# CH2-Input.net
KiCad netlist of a schematic drawn in Altium Designer
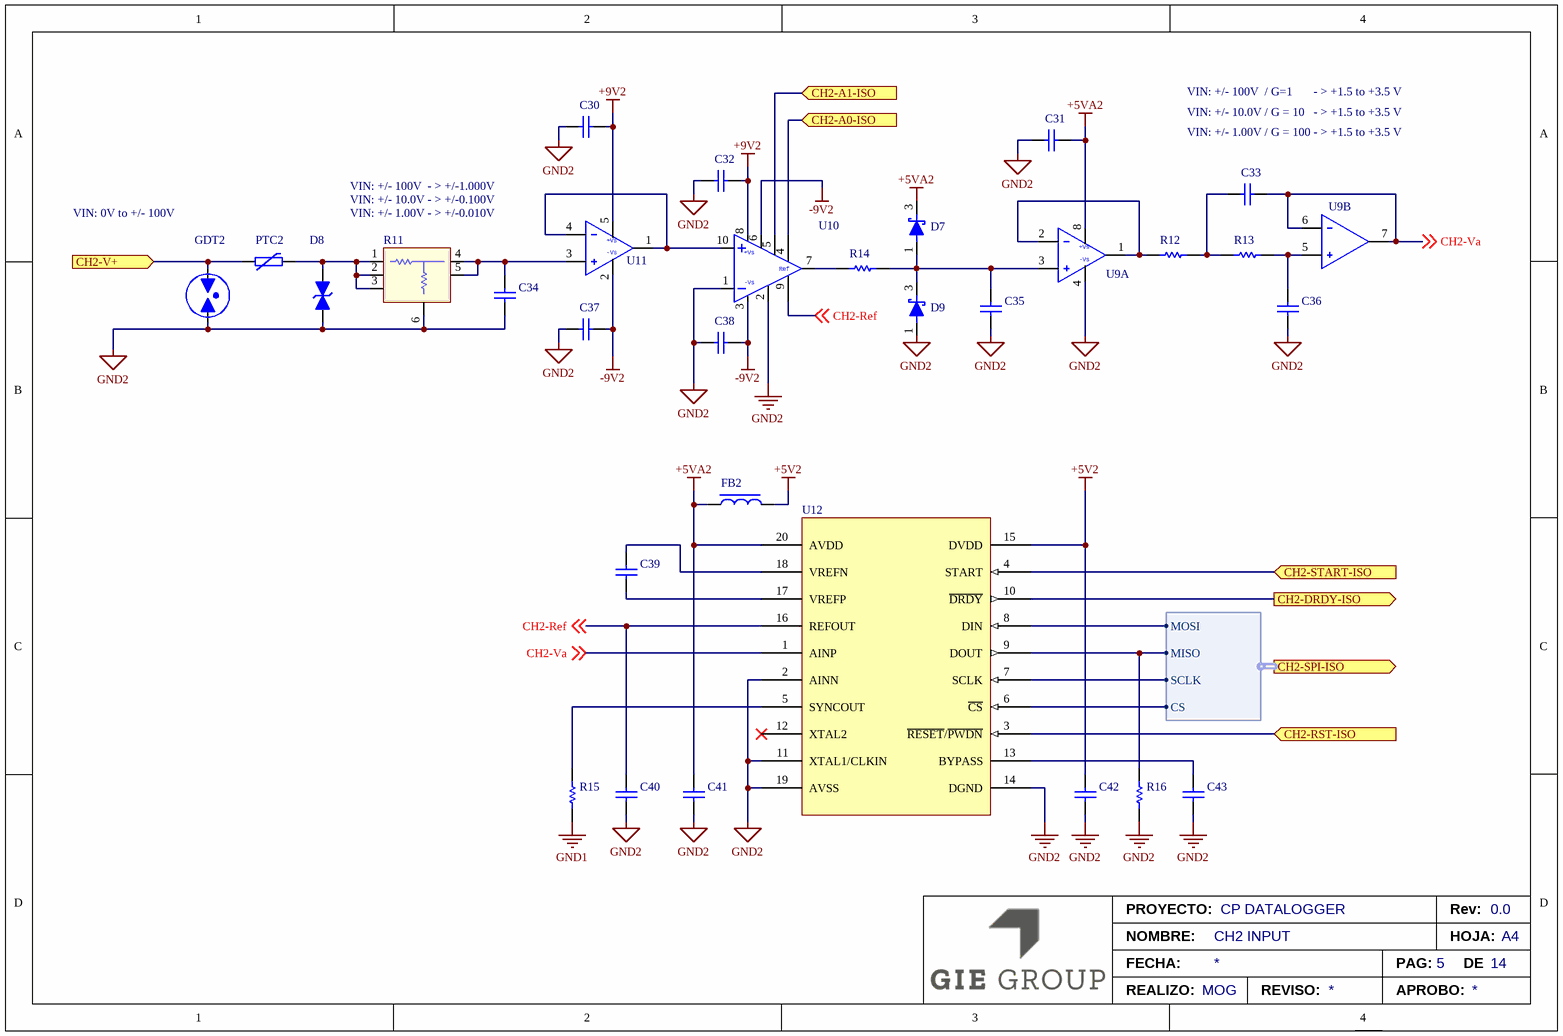
[diagram p0: CH2-Input.SchDoc]

(export (version "E")
  (design (tool "Eeschema 10.0.6"))
  (components
    (comp (ref "C30")
      (value "C0603C104K5RACAUTO")
      (footprint "CAP-0603")
      (description "CAP CER 0.1uF 50V X7R 0603")
      (fields (field (name "MANUFACTURER") "Kemet") (field (name "TOLERANCE") "10%"))
      (libsource (lib "Kemet") (part "C0603C104K5RACAUTO"))
    )
    (comp (ref "C31")
      (value "C0603C104K5RACAUTO")
      (footprint "CAP-0603")
      (description "CAP CER 0.1uF 50V X7R 0603")
      (fields (field (name "MANUFACTURER") "Kemet") (field (name "TOLERANCE") "10%"))
      (libsource (lib "Kemet") (part "C0603C104K5RACAUTO"))
    )
    (comp (ref "C32")
      (value "C0603C104K5RACAUTO")
      (footprint "CAP-0603")
      (description "CAP CER 0.1uF 50V X7R 0603")
      (fields (field (name "MANUFACTURER") "Kemet") (field (name "TOLERANCE") "10%"))
      (libsource (lib "Kemet") (part "C0603C104K5RACAUTO"))
    )
    (comp (ref "C33")
      (value "C0603C162J5GAC7867")
      (footprint "CAP-0603")
      (description "CAP CER 1600´pF 50V C0G 0603")
      (fields (field (name "MANUFACTURER") "Kemet") (field (name "TOLERANCE") "5%"))
      (libsource (lib "Kemet") (part "C0603C162J5GAC7867"))
    )
    (comp (ref "C34")
      (value "C0603C161J1GAC7867")
      (footprint "CAP-0603")
      (description "CAP CER 750´pF 50V C0G 0603")
      (fields (field (name "MANUFACTURER") "Kemet") (field (name "TOLERANCE") "5%"))
      (libsource (lib "Kemet") (part "C0603C751J5GAC7867"))
    )
    (comp (ref "C35")
      (value "C0603C162J5GAC7867")
      (footprint "CAP-0603")
      (description "CAP CER 1600´pF 50V C0G 0603")
      (fields (field (name "MANUFACTURER") "Kemet") (field (name "TOLERANCE") "5%"))
      (libsource (lib "Kemet") (part "C0603C162J5GAC7867"))
    )
    (comp (ref "C36")
      (value "C0603C161J1GAC7867")
      (footprint "CAP-0603")
      (description "CAP CER 160 pF 100V C0G 0603")
      (fields (field (name "MANUFACTURER") "Kemet") (field (name "TOLERANCE") "5%"))
      (libsource (lib "Kemet") (part "C0603C161J1GAC7867"))
    )
    (comp (ref "C37")
      (value "C0603C104K5RACAUTO")
      (footprint "CAP-0603")
      (description "CAP CER 0.1uF 50V X7R 0603")
      (fields (field (name "MANUFACTURER") "Kemet") (field (name "TOLERANCE") "10%"))
      (libsource (lib "Kemet") (part "C0603C104K5RACAUTO"))
    )
    (comp (ref "C38")
      (value "C0603C104K5RACAUTO")
      (footprint "CAP-0603")
      (description "CAP CER 0.1uF 50V X7R 0603")
      (fields (field (name "MANUFACTURER") "Kemet") (field (name "TOLERANCE") "10%"))
      (libsource (lib "Kemet") (part "C0603C104K5RACAUTO"))
    )
    (comp (ref "C39")
      (value "C0603C105M3RAC7867")
      (footprint "CAP-0603")
      (description "CAP CER 1uF 25V X7R 0603")
      (fields (field (name "MANUFACTURER") "Kemet") (field (name "TOLERANCE") "20%"))
      (libsource (lib "Kemet") (part "C0603C105M3RAC7867"))
    )
    (comp (ref "C40")
      (value "C0603C105M3RAC7867")
      (footprint "CAP-0603")
      (description "CAP CER 1uF 25V X7R 0603")
      (fields (field (name "MANUFACTURER") "Kemet") (field (name "TOLERANCE") "20%"))
      (libsource (lib "Kemet") (part "C0603C105M3RAC7867"))
    )
    (comp (ref "C41")
      (value "C0603C105M3RAC7867")
      (footprint "CAP-0603")
      (description "CAP CER 1uF 25V X7R 0603")
      (fields (field (name "MANUFACTURER") "Kemet") (field (name "TOLERANCE") "20%"))
      (libsource (lib "Kemet") (part "C0603C105M3RAC7867"))
    )
    (comp (ref "C42")
      (value "C0603C105M3RAC7867")
      (footprint "CAP-0603")
      (description "CAP CER 1uF 25V X7R 0603")
      (fields (field (name "MANUFACTURER") "Kemet") (field (name "TOLERANCE") "20%"))
      (libsource (lib "Kemet") (part "C0603C105M3RAC7867"))
    )
    (comp (ref "C43")
      (value "C0603C105M3RAC7867")
      (footprint "CAP-0603")
      (description "CAP CER 1uF 25V X7R 0603")
      (fields (field (name "MANUFACTURER") "Kemet") (field (name "TOLERANCE") "20%"))
      (libsource (lib "Kemet") (part "C0603C105M3RAC7867"))
    )
    (comp (ref "D7")
      (value "NSVBAT54WT1G")
      (footprint "SOT-323-3")
      (description "Schottky Diode 30V 200mA SOT323")
      (fields (field (name "MANUFACTURER") "OnSemiconductor"))
      (libsource (lib "OnSemiconductors") (part "NSVBAT54WT1G"))
    )
    (comp (ref "D8")
      (value "~")
      (footprint "SMC - BIIDIR")
      (description "TVS Diode 1.5kW 130V 5% Bi-Directional")
      (fields (field (name "MANUFACTURER") "Littelfuse"))
      (libsource (lib "Littlelfuse") (part "1.5SMC130CA"))
    )
    (comp (ref "D9")
      (value "~")
      (footprint "SOT-323-3")
      (description "Schottky Diode 30V 200mA SOT323")
      (fields (field (name "MANUFACTURER") "OnSemiconductor"))
      (libsource (lib "OnSemiconductors") (part "NSVBAT54WT1G"))
    )
    (comp (ref "FB2")
      (value "Z0603C121GPWZT")
      (footprint "IND-0603")
      (description "Ferrite Bead 120Ohms 900mA 25% DCR=130m")
      (fields (field (name "MANUFACTURER") "Kemet"))
      (libsource (lib "Kemet") (part "Z0603C121GPWZT"))
    )
    (comp (ref "GDT2")
      (value "~")
      (footprint "LITTLELFUSE-CG5XXXLTR")
      (description "Gas Discharge Tube 145V")
      (fields (field (name "MANUFACTURER") "Littelfuse"))
      (libsource (lib "Littlelfuse") (part "CG5145LTR"))
    )
    (comp (ref "PTC2")
      (value "~")
      (footprint "LITTLELFUSE-72R020X")
      (description "PTC Polyfuse Radial 72V 0.2A")
      (fields (field (name "MANUFACTURER") "Littlelfuse"))
      (libsource (lib "Littlelfuse") (part "72R020XPR"))
    )
    (comp (ref "R11")
      (value "~")
      (footprint "CADDOCK - HVD5-B20M-050-05")
      (description "20M ohm 0.05% 5ppm Voltage Divider")
      (fields (field (name "MANUFACTURER") "Caddock"))
      (libsource (lib "Caddock") (part "HVD5-B20M-050-05"))
    )
    (comp (ref "R12")
      (value "RC0603FR-07113KL")
      (footprint "RES-0603")
      (description "RES SMD 113K OHM 1% 1/10W 0603")
      (fields (field (name "TOLERANCE") "1%") (field (name "MANUFACTURER") "Yageo"))
      (libsource (lib "Yageo") (part "RC0603FR-07113KL"))
    )
    (comp (ref "R13")
      (value "RC0603FR-07887KL")
      (footprint "RES-0603")
      (description "RES SMD 887K OHM 1% 1/10W 0603")
      (fields (field (name "TOLERANCE") "1%") (field (name "MANUFACTURER") "Yageo"))
      (libsource (lib "Yageo") (part "RC0603FR-07887KL"))
    )
    (comp (ref "R14")
      (value "RC0603FR-07100KL")
      (footprint "RES-0603")
      (description "RES SMD 100K OHM 1% 1/10W 0603")
      (fields (field (name "TOLERANCE") "1%") (field (name "MANUFACTURER") "Yageo"))
      (libsource (lib "Yageo") (part "RC0603FR-07100KL"))
    )
    (comp (ref "R15")
      (value "RC0603FR-071ML")
      (footprint "RES-0603")
      (description "RES SMD 1M OHM 1% 1/10W 0603")
      (fields (field (name "TOLERANCE") "1%") (field (name "MANUFACTURER") "Yageo"))
      (libsource (lib "Yageo") (part "RC0603FR-071ML"))
    )
    (comp (ref "R16")
      (value "RC0603FR-071ML")
      (footprint "RES-0603")
      (description "RES SMD 1M OHM 1% 1/10W 0603")
      (fields (field (name "TOLERANCE") "1%") (field (name "MANUFACTURER") "Yageo"))
      (libsource (lib "Yageo") (part "RC0603FR-071ML"))
    )
    (comp (ref "U9")
      (value "~")
      (footprint "MSOP8")
      (description "Dual  Precision Amplifier Micro Power Auto Zero")
      (fields (field (name "MANUFACTURER") "Analog Devices"))
      (libsource (lib "AnalogDevices") (part "ADA4051-2ARMZ"))
    )
    (comp (ref "U10")
      (value "AD8253ARMZ")
      (footprint "MSOP10")
      (description "Instrumentation Amplifiers High Speed Programmable High Gain In-Amp")
      (fields (field (name "MANUFACTURER") "Analog Devices Inc"))
      (libsource (lib "AnalogDevices") (part "AD8253ARMZ"))
    )
    (comp (ref "U11")
      (value "~")
      (footprint "SOT23-5")
      (description "16V Auto-Zero CMOS Amplifier")
      (fields (field (name "MANUFACTURER") "Analog Devices"))
      (libsource (lib "AnalogDevices") (part "AD8638ARJZ"))
    )
    (comp (ref "U12")
      (value "~")
      (footprint "TSSOP20")
      (description "Analog to Digital Converter 14.4kSPS 24-Bit")
      (fields (field (name "MANUFACTURER") "Texas Instruments"))
      (libsource (lib "TexasInstruments") (part "ADS1259BIPW"))
    )
  )
  (nets
    (net (code "2") (name "+5V2") (class "Default")
      (node (ref "C42") (pin "2") (pinfunction "2_2") (pintype "passive"))
      (node (ref "FB2") (pin "2") (pinfunction "2_2") (pintype "passive"))
      (node (ref "U12") (pin "15") (pinfunction "DVDD_15") (pintype "power_in"))
    )
    (net (code "3") (name "+5VA2") (class "Default")
      (node (ref "C31") (pin "2") (pinfunction "2_2") (pintype "passive"))
      (node (ref "C41") (pin "2") (pinfunction "2_2") (pintype "passive"))
      (node (ref "D7") (pin "3") (pinfunction "K_3") (pintype "passive"))
      (node (ref "FB2") (pin "1") (pinfunction "1_1") (pintype "passive"))
      (node (ref "U12") (pin "20") (pinfunction "AVDD_20") (pintype "power_in"))
      (node (ref "U9") (pin "8") (pinfunction "+VS_8") (pintype "power_in"))
    )
    (net (code "4") (name "+9V2") (class "Default")
      (node (ref "C30") (pin "2") (pinfunction "2_2") (pintype "passive"))
      (node (ref "C32") (pin "2") (pinfunction "2_2") (pintype "passive"))
      (node (ref "U10") (pin "8") (pinfunction "+Vs_8") (pintype "passive"))
      (node (ref "U11") (pin "5") (pinfunction "+VS_5") (pintype "power_in"))
    )
    (net (code "5") (name "-9V2") (class "Default")
      (node (ref "C37") (pin "2") (pinfunction "2_2") (pintype "passive"))
      (node (ref "C38") (pin "2") (pinfunction "2_2") (pintype "passive"))
      (node (ref "U10") (pin "3") (pinfunction "-Vs_3") (pintype "passive"))
      (node (ref "U10") (pin "6") (pinfunction "WR_6") (pintype "passive"))
      (node (ref "U11") (pin "2") (pinfunction "-Vs_2") (pintype "power_in"))
    )
    (net (code "6") (name "/CH2-A0-ISO") (class "Default")
      (node (ref "U10") (pin "4") (pinfunction "A0_4") (pintype "passive"))
    )
    (net (code "7") (name "/CH2-A1-ISO") (class "Default")
      (node (ref "U10") (pin "5") (pinfunction "A1_5") (pintype "passive"))
    )
    (net (code "8") (name "/CH2-DRDY-ISO") (class "Default")
      (node (ref "U12") (pin "10") (pinfunction "~{DRDY}_10") (pintype "output"))
    )
    (net (code "9") (name "/CH2-RST-ISO") (class "Default")
      (node (ref "U12") (pin "3") (pinfunction "~{RESET}/~{PWDN}_3") (pintype "input"))
    )
    (net (code "10") (name "/CH2-START-ISO") (class "Default")
      (node (ref "U12") (pin "4") (pinfunction "START_4") (pintype "input"))
    )
    (net (code "11") (name "/CH2-V+") (class "Default")
      (node (ref "GDT2") (pin "1") (pinfunction "A_1") (pintype "passive"))
      (node (ref "PTC2") (pin "1") (pinfunction "1_1") (pintype "passive"))
    )
    (net (code "12") (name "/CS") (class "Default")
      (node (ref "U12") (pin "6") (pinfunction "~{CS}_6") (pintype "input"))
    )
    (net (code "13") (name "/MISO") (class "Default")
      (node (ref "R16") (pin "2") (pinfunction "2_2") (pintype "passive"))
      (node (ref "U12") (pin "9") (pinfunction "DOUT_9") (pintype "output"))
    )
    (net (code "14") (name "/MOSI") (class "Default")
      (node (ref "U12") (pin "8") (pinfunction "DIN_8") (pintype "input"))
    )
    (net (code "15") (name "/SCLK") (class "Default")
      (node (ref "U12") (pin "7") (pinfunction "SCLK_7") (pintype "input"))
    )
    (net (code "17") (name "CH2-Ref") (class "Default")
      (node (ref "C40") (pin "2") (pinfunction "2_2") (pintype "passive"))
      (node (ref "U10") (pin "9") (pinfunction "REF_9") (pintype "passive"))
      (node (ref "U12") (pin "16") (pinfunction "REFOUT_16") (pintype "power_in"))
    )
    (net (code "18") (name "CH2-Va") (class "Default")
      (node (ref "C33") (pin "1") (pinfunction "1_1") (pintype "passive"))
      (node (ref "U12") (pin "1") (pinfunction "AINP_1") (pintype "passive"))
      (node (ref "U9") (pin "6") (pinfunction "-INB_6") (pintype "passive"))
      (node (ref "U9") (pin "7") (pinfunction "OUTB_7") (pintype "passive"))
    )
    (net (code "19") (name "GND1") (class "Default")
      (node (ref "R15") (pin "1") (pinfunction "1_1") (pintype "passive"))
    )
    (net (code "20") (name "GND2") (class "Default")
      (node (ref "C30") (pin "1") (pinfunction "1_1") (pintype "passive"))
      (node (ref "C31") (pin "1") (pinfunction "1_1") (pintype "passive"))
      (node (ref "C32") (pin "1") (pinfunction "1_1") (pintype "passive"))
      (node (ref "C34") (pin "1") (pinfunction "1_1") (pintype "passive"))
      (node (ref "C35") (pin "1") (pinfunction "1_1") (pintype "passive"))
      (node (ref "C36") (pin "1") (pinfunction "1_1") (pintype "passive"))
      (node (ref "C37") (pin "1") (pinfunction "1_1") (pintype "passive"))
      (node (ref "C38") (pin "1") (pinfunction "1_1") (pintype "passive"))
      (node (ref "C40") (pin "1") (pinfunction "1_1") (pintype "passive"))
      (node (ref "C41") (pin "1") (pinfunction "1_1") (pintype "passive"))
      (node (ref "C42") (pin "1") (pinfunction "1_1") (pintype "passive"))
      (node (ref "C43") (pin "1") (pinfunction "1_1") (pintype "passive"))
      (node (ref "D8") (pin "2") (pinfunction "K_2") (pintype "passive"))
      (node (ref "D9") (pin "1") (pinfunction "A_1") (pintype "passive"))
      (node (ref "GDT2") (pin "2") (pinfunction "K_2") (pintype "passive"))
      (node (ref "R11") (pin "6") (pinfunction "6_6") (pintype "passive"))
      (node (ref "R16") (pin "1") (pinfunction "1_1") (pintype "passive"))
      (node (ref "U10") (pin "1") (pinfunction "-_IN_1") (pintype "passive"))
      (node (ref "U10") (pin "2") (pinfunction "DGND_2") (pintype "passive"))
      (node (ref "U12") (pin "11") (pinfunction "XTAL1/CLKIN_11") (pintype "power_in"))
      (node (ref "U12") (pin "14") (pinfunction "DGND_14") (pintype "power_in"))
      (node (ref "U12") (pin "19") (pinfunction "AVSS_19") (pintype "power_in"))
      (node (ref "U12") (pin "2") (pinfunction "AINN_2") (pintype "passive"))
      (node (ref "U9") (pin "4") (pinfunction "-Vs_4") (pintype "power_in"))
    )
    (net (code "21") (name "Net-(C33-Pad2)") (class "Default")
      (node (ref "C33") (pin "2") (pinfunction "2_2") (pintype "passive"))
      (node (ref "R12") (pin "2") (pinfunction "2_2") (pintype "passive"))
      (node (ref "R13") (pin "1") (pinfunction "1_1") (pintype "passive"))
    )
    (net (code "22") (name "Net-(D7-A)") (class "Default")
      (node (ref "C35") (pin "2") (pinfunction "2_2") (pintype "passive"))
      (node (ref "D7") (pin "1") (pinfunction "A_1") (pintype "passive"))
      (node (ref "D9") (pin "3") (pinfunction "K_3") (pintype "passive"))
      (node (ref "R14") (pin "2") (pinfunction "2_2") (pintype "passive"))
      (node (ref "U9") (pin "3") (pinfunction "+INA_3") (pintype "passive"))
    )
    (net (code "23") (name "Net-(D8-A)") (class "Default")
      (node (ref "D8") (pin "1") (pinfunction "A_1") (pintype "passive"))
      (node (ref "PTC2") (pin "2") (pinfunction "2_2") (pintype "passive"))
      (node (ref "R11") (pin "1") (pinfunction "1_1") (pintype "passive"))
      (node (ref "R11") (pin "2") (pinfunction "2_2") (pintype "passive"))
      (node (ref "R11") (pin "3") (pinfunction "3_3") (pintype "passive"))
    )
    (net (code "24") (name "Net-(U9A--INA)") (class "Default")
      (node (ref "R12") (pin "1") (pinfunction "1_1") (pintype "passive"))
      (node (ref "U9") (pin "1") (pinfunction "OUTA_1") (pintype "passive"))
      (node (ref "U9") (pin "2") (pinfunction "-INA_2") (pintype "passive"))
    )
    (net (code "25") (name "Net-(U9B-+INB)") (class "Default")
      (node (ref "C36") (pin "2") (pinfunction "2_2") (pintype "passive"))
      (node (ref "R13") (pin "2") (pinfunction "2_2") (pintype "passive"))
      (node (ref "U9") (pin "5") (pinfunction "+INB_5") (pintype "passive"))
    )
    (net (code "26") (name "Net-(U10-+_IN)") (class "Default")
      (node (ref "U10") (pin "10") (pinfunction "+_IN_10") (pintype "passive"))
      (node (ref "U11") (pin "1") (pinfunction "OUT_1") (pintype "passive"))
      (node (ref "U11") (pin "4") (pinfunction "-IN_4") (pintype "passive"))
    )
    (net (code "27") (name "Net-(U10-OUT)") (class "Default")
      (node (ref "R14") (pin "1") (pinfunction "1_1") (pintype "passive"))
      (node (ref "U10") (pin "7") (pinfunction "OUT_7") (pintype "passive"))
    )
    (net (code "28") (name "Net-(U11-+IN)") (class "Default")
      (node (ref "C34") (pin "2") (pinfunction "2_2") (pintype "passive"))
      (node (ref "R11") (pin "4") (pinfunction "4_4") (pintype "passive"))
      (node (ref "R11") (pin "5") (pinfunction "5_5") (pintype "passive"))
      (node (ref "U11") (pin "3") (pinfunction "+IN_3") (pintype "passive"))
    )
    (net (code "29") (name "Net-(U12-BYPASS)") (class "Default")
      (node (ref "C43") (pin "2") (pinfunction "2_2") (pintype "passive"))
      (node (ref "U12") (pin "13") (pinfunction "BYPASS_13") (pintype "power_in"))
    )
    (net (code "30") (name "Net-(U12-SYNCOUT)") (class "Default")
      (node (ref "R15") (pin "2") (pinfunction "2_2") (pintype "passive"))
      (node (ref "U12") (pin "5") (pinfunction "SYNCOUT_5") (pintype "passive"))
    )
    (net (code "31") (name "Net-(U12-VREFN)") (class "Default")
      (node (ref "C39") (pin "2") (pinfunction "2_2") (pintype "passive"))
      (node (ref "U12") (pin "18") (pinfunction "VREFN_18") (pintype "power_in"))
    )
    (net (code "32") (name "Net-(U12-VREFP)") (class "Default")
      (node (ref "C39") (pin "1") (pinfunction "1_1") (pintype "passive"))
      (node (ref "U12") (pin "17") (pinfunction "VREFP_17") (pintype "power_in"))
    )
    (net (code "33") (name "unconnected-(U12-XTAL2-Pad12)") (class "Default")
      (node (ref "U12") (pin "12") (pinfunction "XTAL2_12") (pintype "power_in+no_connect"))
    )
  )
)
